# Regulador.net
KiCad netlist of a schematic drawn in Altium Designer
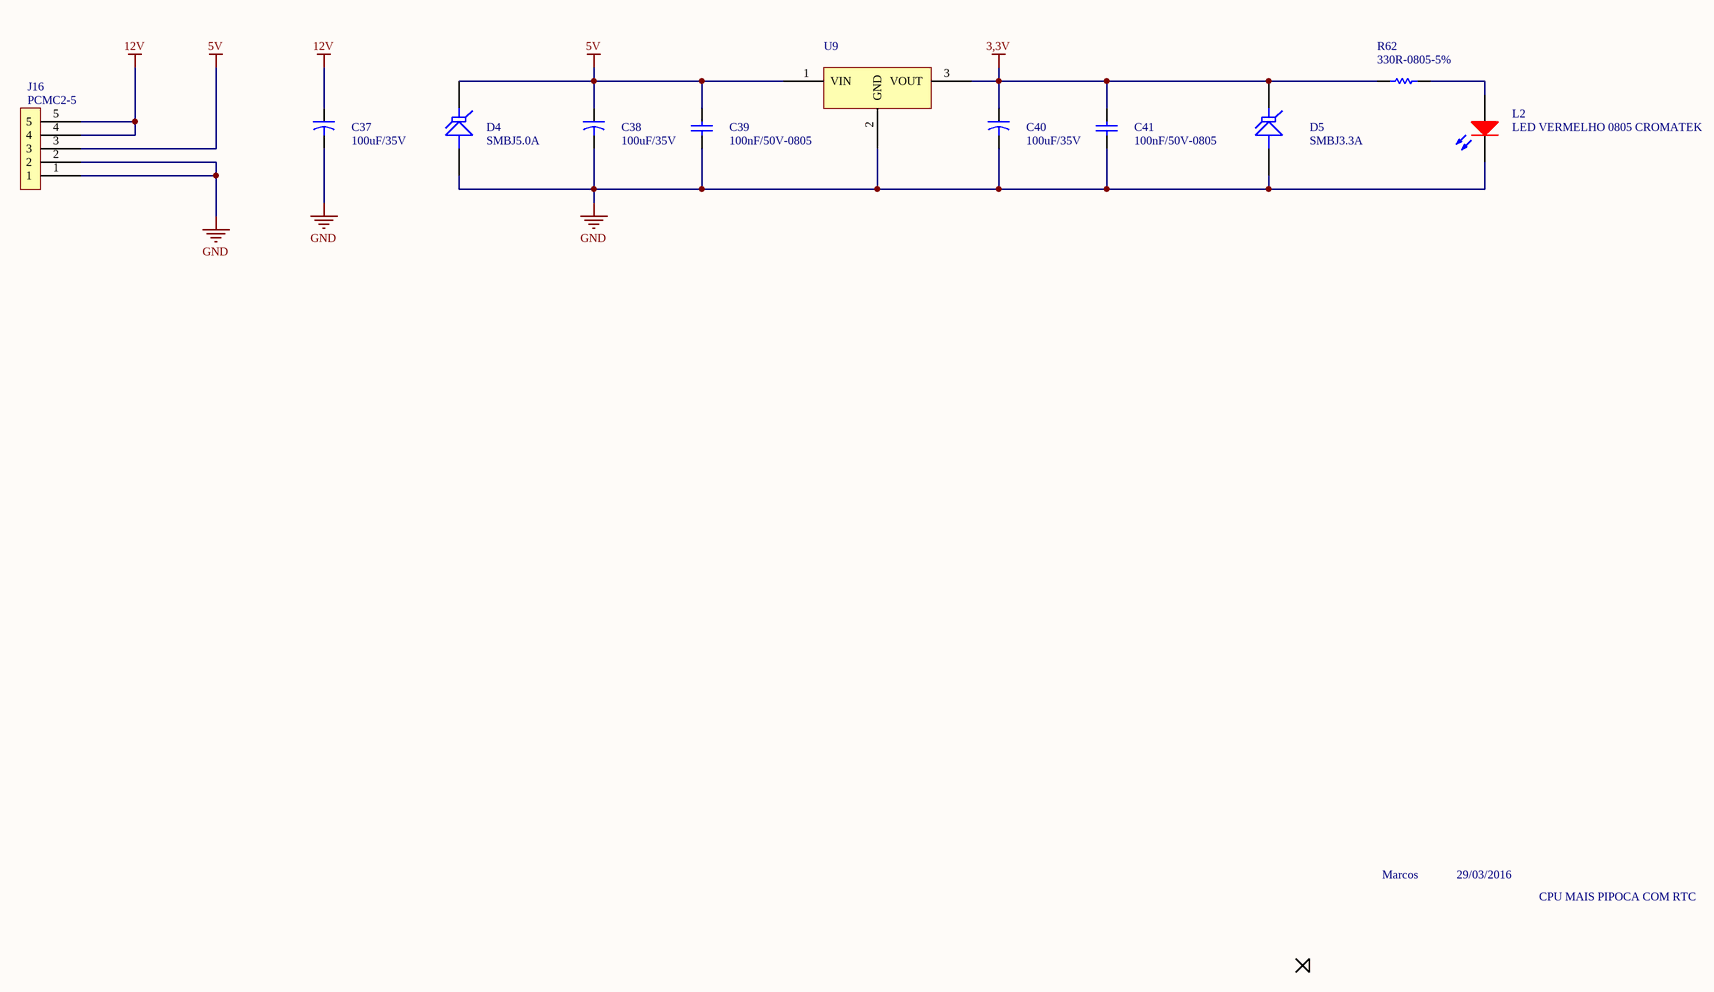
[diagram p0: Regulador.SchDoc]

(export (version "E")
  (design (tool "Eeschema 10.0.6"))
  (components
    (comp (ref "C37")
      (value "100uF/35V")
      (footprint "CAP POL 8x12mm")
      (description "100uF/50V")
      (libsource (lib "AquinoLib") (part "100uF/50V"))
    )
    (comp (ref "C38")
      (value "100uF/35V")
      (footprint "CAP POL 8x12mm")
      (description "100uF/50V")
      (libsource (lib "AquinoLib") (part "100uF/50V"))
    )
    (comp (ref "C39")
      (value "100nF/50V-0805")
      (footprint "0805-REVISADO O")
      (description "100nF/50-0805-NPO")
      (libsource (lib "AquinoLib") (part "100nF/50-0805-NPO"))
    )
    (comp (ref "C40")
      (value "100uF/35V")
      (footprint "CAP POL 8x12mm")
      (description "100uF/50V")
      (libsource (lib "AquinoLib") (part "100uF/50V"))
    )
    (comp (ref "C41")
      (value "100nF/50V-0805")
      (footprint "0805-REVISADO O")
      (description "100nF/50-0805-NPO")
      (libsource (lib "AquinoLib") (part "100nF/50-0805-NPO"))
    )
    (comp (ref "D4")
      (value "SMBJ5.0A")
      (footprint "SMB/DO214AA-REV")
      (libsource (lib "AquinoLib") (part "SMBJ5.0A"))
    )
    (comp (ref "D5")
      (value "SMBJ3.3A")
      (footprint "SMB/DO214AA-REV")
      (description "SMBJ5.0A")
      (libsource (lib "AquinoLib") (part "SMBJ5.0A"))
    )
    (comp (ref "J16") (value "PCMC2-5") (footprint "PCMC2-5") (libsource (lib "AquinoLib") (part "PCMC2-5")))
    (comp (ref "L2")
      (value "LED VERMELHO 0805 CROMATEK")
      (footprint "LED 0805 - REVI")
      (description "LED VERMELHO 0603 SMD")
      (libsource (lib "AquinoLib") (part "LED VERMELHO 0603 SMD"))
    )
    (comp (ref "R62")
      (value "330R-0805-5%")
      (footprint "0805-REVISADO O")
      (description "1K-0805-5%")
      (libsource (lib "AquinoLib") (part "1K-0805-5%"))
    )
    (comp (ref "U9")
      (value "~")
      (footprint "TO-263_3")
      (description "LM3940IT-3.3-TO220")
      (libsource (lib "ChaveDigital3") (part "LM3940IT-3.3-TO220"))
    )
  )
  (nets
    (net (code "1") (name "3,3V") (class "Default")
      (node (ref "C40") (pin "1") (pinfunction "1_1") (pintype "passive"))
      (node (ref "C41") (pin "2") (pinfunction "2_2") (pintype "passive"))
      (node (ref "D5") (pin "2") (pinfunction "K_2") (pintype "passive"))
      (node (ref "R62") (pin "1") (pinfunction "1_1") (pintype "passive"))
      (node (ref "U9") (pin "3") (pinfunction "VOUT_3") (pintype "passive"))
    )
    (net (code "2") (name "5V") (class "Default")
      (node (ref "C38") (pin "1") (pinfunction "1_1") (pintype "passive"))
      (node (ref "C39") (pin "2") (pinfunction "2_2") (pintype "passive"))
      (node (ref "D4") (pin "2") (pinfunction "K_2") (pintype "passive"))
      (node (ref "J16") (pin "3") (pinfunction "3_3") (pintype "passive"))
      (node (ref "U9") (pin "1") (pinfunction "VIN_1") (pintype "passive"))
    )
    (net (code "3") (name "12V") (class "Default")
      (node (ref "C37") (pin "1") (pinfunction "1_1") (pintype "passive"))
      (node (ref "J16") (pin "4") (pinfunction "4_4") (pintype "passive"))
      (node (ref "J16") (pin "5") (pinfunction "5_5") (pintype "passive"))
    )
    (net (code "4") (name "GND") (class "Default")
      (node (ref "C37") (pin "2") (pinfunction "2_2") (pintype "passive"))
      (node (ref "C38") (pin "2") (pinfunction "2_2") (pintype "passive"))
      (node (ref "C39") (pin "1") (pinfunction "1_1") (pintype "passive"))
      (node (ref "C40") (pin "2") (pinfunction "2_2") (pintype "passive"))
      (node (ref "C41") (pin "1") (pinfunction "1_1") (pintype "passive"))
      (node (ref "D4") (pin "1") (pinfunction "A_1") (pintype "passive"))
      (node (ref "D5") (pin "1") (pinfunction "A_1") (pintype "passive"))
      (node (ref "J16") (pin "1") (pinfunction "1_1") (pintype "passive"))
      (node (ref "J16") (pin "2") (pinfunction "2_2") (pintype "passive"))
      (node (ref "L2") (pin "2") (pinfunction "K_2") (pintype "passive"))
      (node (ref "U9") (pin "2") (pinfunction "GND_2") (pintype "passive"))
    )
    (net (code "5") (name "Net-(L2-A)") (class "Default")
      (node (ref "L2") (pin "1") (pinfunction "A_1") (pintype "passive"))
      (node (ref "R62") (pin "2") (pinfunction "2_2") (pintype "passive"))
    )
  )
)
